# PS_DDR.net
KiCad netlist of a schematic drawn in Altium Designer
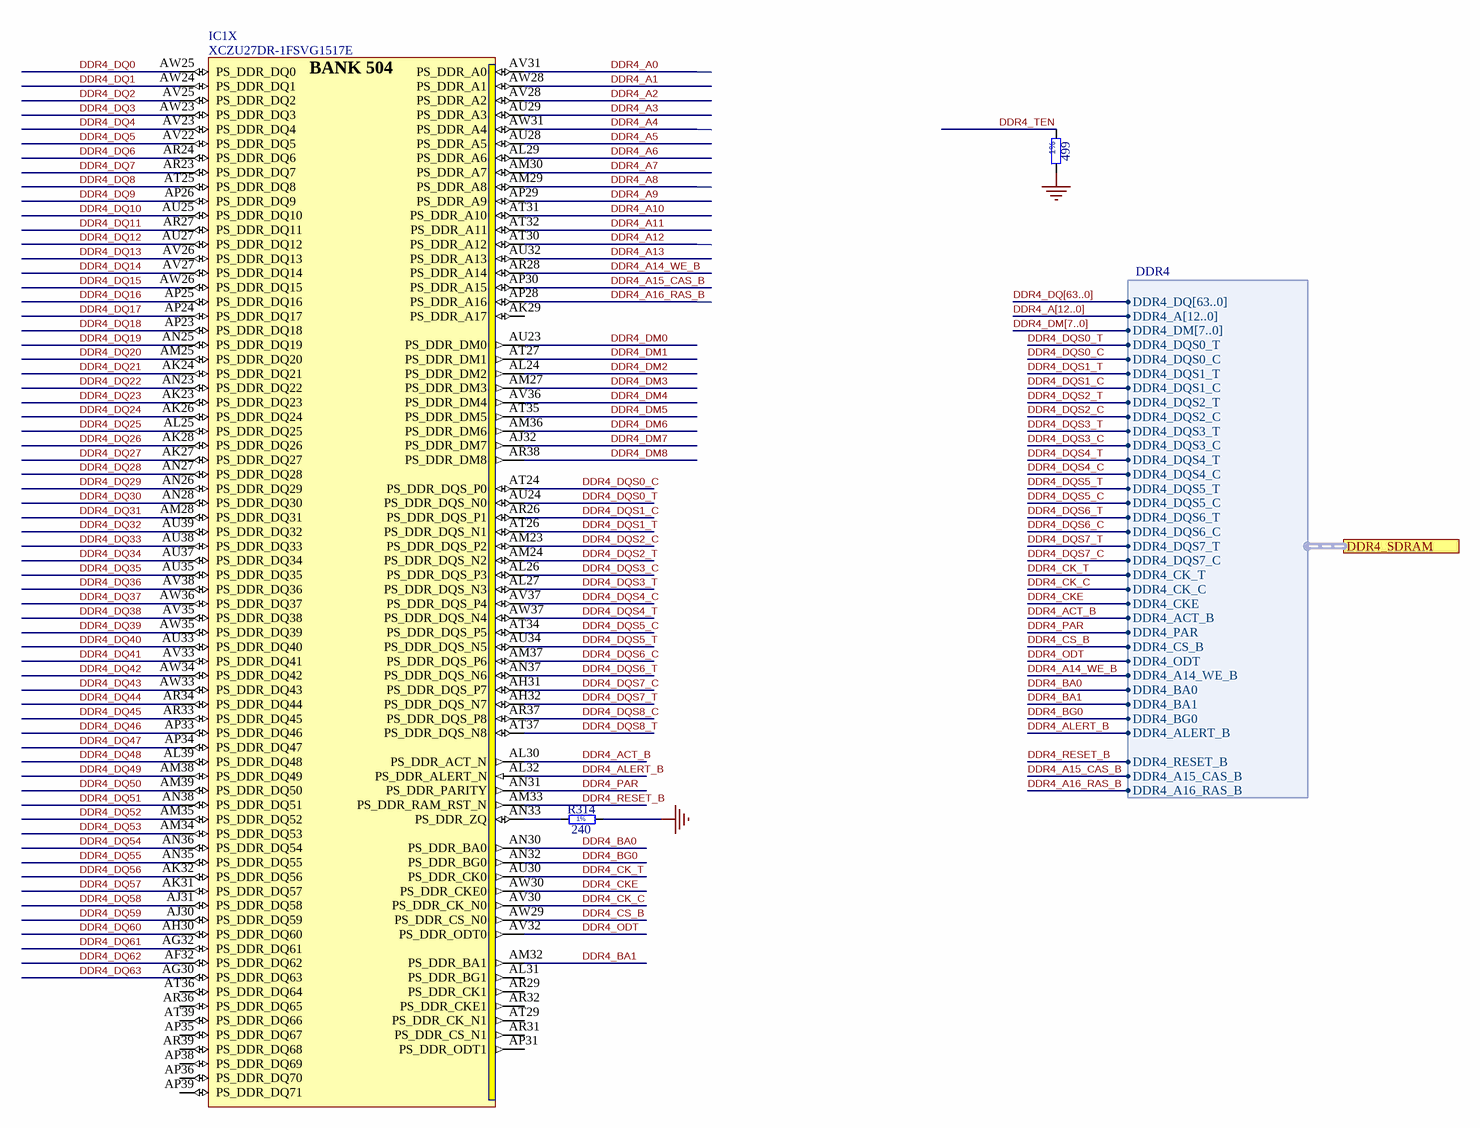
[diagram p0: PS_DDR.SchDoc]

(export (version "E")
  (design (tool "Eeschema 10.0.6"))
  (components
    (comp (ref "IC1")
      (value "XCZU27DR-1FSVG1517E")
      (footprint "XILINX_FSVG1517 (XCZU27DR)")
      (fields (field (name "MANUFACTURER") "XILINX") (field (name "AUTHOR") "CERN DEM MR"))
      (libsource (lib "ICs And Semiconductors") (part "XCZU27DR-1FSVG1517E"))
    )
    (comp (ref "R314")
      (value "240")
      (footprint "RESC1005X40N")
      (description "Resistor - 1%")
      (fields
        (field (name "MANUFACTURER PART NUMBER") "R0402_240R_1%_0.0625W_100PPM")
        (field (name "MANUFACTURER") "GENERIC")
        (field (name "AUTHOR") "CERN DEM JLC")
      )
      (libsource (lib "Resistors") (part "Resistor - 1%"))
    )
    (comp (ref "R629")
      (value "499")
      (fields
        (field (name "$$NOTCOMMONPROPERTY_GENERAL PART NUMBER") "R0402_499R_1%_0.063W_100PPM")
        (field (name "$$NOTCOMMONPROPERTY_MANUFACTURER1 PART NUMBER") "RC0402FR-07499RL")
        (field (name "MANUFACTURER PART NUMBER") "R0402_499R_1%_0.0625W_100PPM")
      )
      (libsource (lib "altium-import") (part "root_1__*"))
    )
  )
  (nets
    (net (code "2") (name "/DDR4_A0") (class "Default")
      (node (ref "IC1") (pin "AV31") (pinfunction "PS_DDR_A0_AV31") (pintype "bidirectional"))
    )
    (net (code "3") (name "/DDR4_A1") (class "Default")
      (node (ref "IC1") (pin "AW28") (pinfunction "PS_DDR_A1_AW28") (pintype "bidirectional"))
    )
    (net (code "4") (name "/DDR4_A2") (class "Default")
      (node (ref "IC1") (pin "AV28") (pinfunction "PS_DDR_A2_AV28") (pintype "bidirectional"))
    )
    (net (code "5") (name "/DDR4_A3") (class "Default")
      (node (ref "IC1") (pin "AU29") (pinfunction "PS_DDR_A3_AU29") (pintype "bidirectional"))
    )
    (net (code "6") (name "/DDR4_A4") (class "Default")
      (node (ref "IC1") (pin "AW31") (pinfunction "PS_DDR_A4_AW31") (pintype "bidirectional"))
    )
    (net (code "7") (name "/DDR4_A5") (class "Default")
      (node (ref "IC1") (pin "AU28") (pinfunction "PS_DDR_A5_AU28") (pintype "bidirectional"))
    )
    (net (code "8") (name "/DDR4_A6") (class "Default")
      (node (ref "IC1") (pin "AL29") (pinfunction "PS_DDR_A6_AL29") (pintype "bidirectional"))
    )
    (net (code "9") (name "/DDR4_A7") (class "Default")
      (node (ref "IC1") (pin "AM30") (pinfunction "PS_DDR_A7_AM30") (pintype "bidirectional"))
    )
    (net (code "10") (name "/DDR4_A8") (class "Default")
      (node (ref "IC1") (pin "AM29") (pinfunction "PS_DDR_A8_AM29") (pintype "bidirectional"))
    )
    (net (code "11") (name "/DDR4_A9") (class "Default")
      (node (ref "IC1") (pin "AP29") (pinfunction "PS_DDR_A9_AP29") (pintype "bidirectional"))
    )
    (net (code "12") (name "/DDR4_A10") (class "Default")
      (node (ref "IC1") (pin "AT31") (pinfunction "PS_DDR_A10_AT31") (pintype "bidirectional"))
    )
    (net (code "13") (name "/DDR4_A11") (class "Default")
      (node (ref "IC1") (pin "AT32") (pinfunction "PS_DDR_A11_AT32") (pintype "bidirectional"))
    )
    (net (code "14") (name "/DDR4_A12") (class "Default")
      (node (ref "IC1") (pin "AT30") (pinfunction "PS_DDR_A12_AT30") (pintype "bidirectional"))
    )
    (net (code "15") (name "/DDR4_A13") (class "Default")
      (node (ref "IC1") (pin "AU32") (pinfunction "PS_DDR_A13_AU32") (pintype "bidirectional"))
    )
    (net (code "16") (name "/DDR4_A14_WE_B") (class "Default")
      (node (ref "IC1") (pin "AR28") (pinfunction "PS_DDR_A14_AR28") (pintype "bidirectional"))
    )
    (net (code "17") (name "/DDR4_A15_CAS_B") (class "Default")
      (node (ref "IC1") (pin "AP30") (pinfunction "PS_DDR_A15_AP30") (pintype "bidirectional"))
    )
    (net (code "18") (name "/DDR4_A16_RAS_B") (class "Default")
      (node (ref "IC1") (pin "AP28") (pinfunction "PS_DDR_A16_AP28") (pintype "bidirectional"))
    )
    (net (code "19") (name "/DDR4_ACT_B") (class "Default")
      (node (ref "IC1") (pin "AL30") (pinfunction "PS_DDR_ACT_N_AL30") (pintype "output"))
    )
    (net (code "20") (name "/DDR4_ALERT_B") (class "Default")
      (node (ref "IC1") (pin "AL32") (pinfunction "PS_DDR_ALERT_N_AL32") (pintype "input"))
    )
    (net (code "22") (name "/DDR4_BA0") (class "Default")
      (node (ref "IC1") (pin "AN30") (pinfunction "PS_DDR_BA0_AN30") (pintype "output"))
    )
    (net (code "23") (name "/DDR4_BA1") (class "Default")
      (node (ref "IC1") (pin "AM32") (pinfunction "PS_DDR_BA1_AM32") (pintype "output"))
    )
    (net (code "24") (name "/DDR4_BG0") (class "Default")
      (node (ref "IC1") (pin "AN32") (pinfunction "PS_DDR_BG0_AN32") (pintype "output"))
    )
    (net (code "25") (name "/DDR4_CKE") (class "Default")
      (node (ref "IC1") (pin "AW30") (pinfunction "PS_DDR_CKE0_AW30") (pintype "output"))
    )
    (net (code "26") (name "/DDR4_CK_C") (class "Default")
      (node (ref "IC1") (pin "AV30") (pinfunction "PS_DDR_CK_N0_AV30") (pintype "output"))
    )
    (net (code "27") (name "/DDR4_CK_T") (class "Default")
      (node (ref "IC1") (pin "AU30") (pinfunction "PS_DDR_CK0_AU30") (pintype "output"))
    )
    (net (code "28") (name "/DDR4_CS_B") (class "Default")
      (node (ref "IC1") (pin "AW29") (pinfunction "PS_DDR_CS_N0_AW29") (pintype "output"))
    )
    (net (code "29") (name "/DDR4_DM0") (class "Default")
      (node (ref "IC1") (pin "AU23") (pinfunction "PS_DDR_DM0_AU23") (pintype "output"))
    )
    (net (code "30") (name "/DDR4_DM1") (class "Default")
      (node (ref "IC1") (pin "AT27") (pinfunction "PS_DDR_DM1_AT27") (pintype "output"))
    )
    (net (code "31") (name "/DDR4_DM2") (class "Default")
      (node (ref "IC1") (pin "AL24") (pinfunction "PS_DDR_DM2_AL24") (pintype "output"))
    )
    (net (code "32") (name "/DDR4_DM3") (class "Default")
      (node (ref "IC1") (pin "AM27") (pinfunction "PS_DDR_DM3_AM27") (pintype "output"))
    )
    (net (code "33") (name "/DDR4_DM4") (class "Default")
      (node (ref "IC1") (pin "AV36") (pinfunction "PS_DDR_DM4_AV36") (pintype "output"))
    )
    (net (code "34") (name "/DDR4_DM5") (class "Default")
      (node (ref "IC1") (pin "AT35") (pinfunction "PS_DDR_DM5_AT35") (pintype "output"))
    )
    (net (code "35") (name "/DDR4_DM6") (class "Default")
      (node (ref "IC1") (pin "AM36") (pinfunction "PS_DDR_DM6_AM36") (pintype "output"))
    )
    (net (code "36") (name "/DDR4_DM7") (class "Default")
      (node (ref "IC1") (pin "AJ32") (pinfunction "PS_DDR_DM7_AJ32") (pintype "output"))
    )
    (net (code "37") (name "/DDR4_DM8") (class "Default")
      (node (ref "IC1") (pin "AR38") (pinfunction "PS_DDR_DM8_AR38") (pintype "output"))
    )
    (net (code "39") (name "/DDR4_DQ0") (class "Default")
      (node (ref "IC1") (pin "AW25") (pinfunction "PS_DDR_DQ0_AW25") (pintype "bidirectional"))
    )
    (net (code "40") (name "/DDR4_DQ1") (class "Default")
      (node (ref "IC1") (pin "AW24") (pinfunction "PS_DDR_DQ1_AW24") (pintype "bidirectional"))
    )
    (net (code "41") (name "/DDR4_DQ2") (class "Default")
      (node (ref "IC1") (pin "AV25") (pinfunction "PS_DDR_DQ2_AV25") (pintype "bidirectional"))
    )
    (net (code "42") (name "/DDR4_DQ3") (class "Default")
      (node (ref "IC1") (pin "AW23") (pinfunction "PS_DDR_DQ3_AW23") (pintype "bidirectional"))
    )
    (net (code "43") (name "/DDR4_DQ4") (class "Default")
      (node (ref "IC1") (pin "AV23") (pinfunction "PS_DDR_DQ4_AV23") (pintype "bidirectional"))
    )
    (net (code "44") (name "/DDR4_DQ5") (class "Default")
      (node (ref "IC1") (pin "AV22") (pinfunction "PS_DDR_DQ5_AV22") (pintype "bidirectional"))
    )
    (net (code "45") (name "/DDR4_DQ6") (class "Default")
      (node (ref "IC1") (pin "AR24") (pinfunction "PS_DDR_DQ6_AR24") (pintype "bidirectional"))
    )
    (net (code "46") (name "/DDR4_DQ7") (class "Default")
      (node (ref "IC1") (pin "AR23") (pinfunction "PS_DDR_DQ7_AR23") (pintype "bidirectional"))
    )
    (net (code "47") (name "/DDR4_DQ8") (class "Default")
      (node (ref "IC1") (pin "AT25") (pinfunction "PS_DDR_DQ8_AT25") (pintype "bidirectional"))
    )
    (net (code "48") (name "/DDR4_DQ9") (class "Default")
      (node (ref "IC1") (pin "AP26") (pinfunction "PS_DDR_DQ9_AP26") (pintype "bidirectional"))
    )
    (net (code "49") (name "/DDR4_DQ10") (class "Default")
      (node (ref "IC1") (pin "AU25") (pinfunction "PS_DDR_DQ10_AU25") (pintype "bidirectional"))
    )
    (net (code "50") (name "/DDR4_DQ11") (class "Default")
      (node (ref "IC1") (pin "AR27") (pinfunction "PS_DDR_DQ11_AR27") (pintype "bidirectional"))
    )
    (net (code "51") (name "/DDR4_DQ12") (class "Default")
      (node (ref "IC1") (pin "AU27") (pinfunction "PS_DDR_DQ12_AU27") (pintype "bidirectional"))
    )
    (net (code "52") (name "/DDR4_DQ13") (class "Default")
      (node (ref "IC1") (pin "AV26") (pinfunction "PS_DDR_DQ13_AV26") (pintype "bidirectional"))
    )
    (net (code "53") (name "/DDR4_DQ14") (class "Default")
      (node (ref "IC1") (pin "AV27") (pinfunction "PS_DDR_DQ14_AV27") (pintype "bidirectional"))
    )
    (net (code "54") (name "/DDR4_DQ15") (class "Default")
      (node (ref "IC1") (pin "AW26") (pinfunction "PS_DDR_DQ15_AW26") (pintype "bidirectional"))
    )
    (net (code "55") (name "/DDR4_DQ16") (class "Default")
      (node (ref "IC1") (pin "AP25") (pinfunction "PS_DDR_DQ16_AP25") (pintype "bidirectional"))
    )
    (net (code "56") (name "/DDR4_DQ17") (class "Default")
      (node (ref "IC1") (pin "AP24") (pinfunction "PS_DDR_DQ17_AP24") (pintype "bidirectional"))
    )
    (net (code "57") (name "/DDR4_DQ18") (class "Default")
      (node (ref "IC1") (pin "AP23") (pinfunction "PS_DDR_DQ18_AP23") (pintype "bidirectional"))
    )
    (net (code "58") (name "/DDR4_DQ19") (class "Default")
      (node (ref "IC1") (pin "AN25") (pinfunction "PS_DDR_DQ19_AN25") (pintype "bidirectional"))
    )
    (net (code "59") (name "/DDR4_DQ20") (class "Default")
      (node (ref "IC1") (pin "AM25") (pinfunction "PS_DDR_DQ20_AM25") (pintype "bidirectional"))
    )
    (net (code "60") (name "/DDR4_DQ21") (class "Default")
      (node (ref "IC1") (pin "AK24") (pinfunction "PS_DDR_DQ21_AK24") (pintype "bidirectional"))
    )
    (net (code "61") (name "/DDR4_DQ22") (class "Default")
      (node (ref "IC1") (pin "AN23") (pinfunction "PS_DDR_DQ22_AN23") (pintype "bidirectional"))
    )
    (net (code "62") (name "/DDR4_DQ23") (class "Default")
      (node (ref "IC1") (pin "AK23") (pinfunction "PS_DDR_DQ23_AK23") (pintype "bidirectional"))
    )
    (net (code "63") (name "/DDR4_DQ24") (class "Default")
      (node (ref "IC1") (pin "AK26") (pinfunction "PS_DDR_DQ24_AK26") (pintype "bidirectional"))
    )
    (net (code "64") (name "/DDR4_DQ25") (class "Default")
      (node (ref "IC1") (pin "AL25") (pinfunction "PS_DDR_DQ25_AL25") (pintype "bidirectional"))
    )
    (net (code "65") (name "/DDR4_DQ26") (class "Default")
      (node (ref "IC1") (pin "AK28") (pinfunction "PS_DDR_DQ26_AK28") (pintype "bidirectional"))
    )
    (net (code "66") (name "/DDR4_DQ27") (class "Default")
      (node (ref "IC1") (pin "AK27") (pinfunction "PS_DDR_DQ27_AK27") (pintype "bidirectional"))
    )
    (net (code "67") (name "/DDR4_DQ28") (class "Default")
      (node (ref "IC1") (pin "AN27") (pinfunction "PS_DDR_DQ28_AN27") (pintype "bidirectional"))
    )
    (net (code "68") (name "/DDR4_DQ29") (class "Default")
      (node (ref "IC1") (pin "AN26") (pinfunction "PS_DDR_DQ29_AN26") (pintype "bidirectional"))
    )
    (net (code "69") (name "/DDR4_DQ30") (class "Default")
      (node (ref "IC1") (pin "AN28") (pinfunction "PS_DDR_DQ30_AN28") (pintype "bidirectional"))
    )
    (net (code "70") (name "/DDR4_DQ31") (class "Default")
      (node (ref "IC1") (pin "AM28") (pinfunction "PS_DDR_DQ31_AM28") (pintype "bidirectional"))
    )
    (net (code "71") (name "/DDR4_DQ32") (class "Default")
      (node (ref "IC1") (pin "AU39") (pinfunction "PS_DDR_DQ32_AU39") (pintype "bidirectional"))
    )
    (net (code "72") (name "/DDR4_DQ33") (class "Default")
      (node (ref "IC1") (pin "AU38") (pinfunction "PS_DDR_DQ33_AU38") (pintype "bidirectional"))
    )
    (net (code "73") (name "/DDR4_DQ34") (class "Default")
      (node (ref "IC1") (pin "AU37") (pinfunction "PS_DDR_DQ34_AU37") (pintype "bidirectional"))
    )
    (net (code "74") (name "/DDR4_DQ35") (class "Default")
      (node (ref "IC1") (pin "AU35") (pinfunction "PS_DDR_DQ35_AU35") (pintype "bidirectional"))
    )
    (net (code "75") (name "/DDR4_DQ36") (class "Default")
      (node (ref "IC1") (pin "AV38") (pinfunction "PS_DDR_DQ36_AV38") (pintype "bidirectional"))
    )
    (net (code "76") (name "/DDR4_DQ37") (class "Default")
      (node (ref "IC1") (pin "AW36") (pinfunction "PS_DDR_DQ37_AW36") (pintype "bidirectional"))
    )
    (net (code "77") (name "/DDR4_DQ38") (class "Default")
      (node (ref "IC1") (pin "AV35") (pinfunction "PS_DDR_DQ38_AV35") (pintype "bidirectional"))
    )
    (net (code "78") (name "/DDR4_DQ39") (class "Default")
      (node (ref "IC1") (pin "AW35") (pinfunction "PS_DDR_DQ39_AW35") (pintype "bidirectional"))
    )
    (net (code "79") (name "/DDR4_DQ40") (class "Default")
      (node (ref "IC1") (pin "AU33") (pinfunction "PS_DDR_DQ40_AU33") (pintype "bidirectional"))
    )
    (net (code "80") (name "/DDR4_DQ41") (class "Default")
      (node (ref "IC1") (pin "AV33") (pinfunction "PS_DDR_DQ41_AV33") (pintype "bidirectional"))
    )
    (net (code "81") (name "/DDR4_DQ42") (class "Default")
      (node (ref "IC1") (pin "AW34") (pinfunction "PS_DDR_DQ42_AW34") (pintype "bidirectional"))
    )
    (net (code "82") (name "/DDR4_DQ43") (class "Default")
      (node (ref "IC1") (pin "AW33") (pinfunction "PS_DDR_DQ43_AW33") (pintype "bidirectional"))
    )
    (net (code "83") (name "/DDR4_DQ44") (class "Default")
      (node (ref "IC1") (pin "AR34") (pinfunction "PS_DDR_DQ44_AR34") (pintype "bidirectional"))
    )
    (net (code "84") (name "/DDR4_DQ45") (class "Default")
      (node (ref "IC1") (pin "AR33") (pinfunction "PS_DDR_DQ45_AR33") (pintype "bidirectional"))
    )
    (net (code "85") (name "/DDR4_DQ46") (class "Default")
      (node (ref "IC1") (pin "AP33") (pinfunction "PS_DDR_DQ46_AP33") (pintype "bidirectional"))
    )
    (net (code "86") (name "/DDR4_DQ47") (class "Default")
      (node (ref "IC1") (pin "AP34") (pinfunction "PS_DDR_DQ47_AP34") (pintype "bidirectional"))
    )
    (net (code "87") (name "/DDR4_DQ48") (class "Default")
      (node (ref "IC1") (pin "AL39") (pinfunction "PS_DDR_DQ48_AL39") (pintype "bidirectional"))
    )
    (net (code "88") (name "/DDR4_DQ49") (class "Default")
      (node (ref "IC1") (pin "AM38") (pinfunction "PS_DDR_DQ49_AM38") (pintype "bidirectional"))
    )
    (net (code "89") (name "/DDR4_DQ50") (class "Default")
      (node (ref "IC1") (pin "AM39") (pinfunction "PS_DDR_DQ50_AM39") (pintype "bidirectional"))
    )
    (net (code "90") (name "/DDR4_DQ51") (class "Default")
      (node (ref "IC1") (pin "AN38") (pinfunction "PS_DDR_DQ51_AN38") (pintype "bidirectional"))
    )
    (net (code "91") (name "/DDR4_DQ52") (class "Default")
      (node (ref "IC1") (pin "AM35") (pinfunction "PS_DDR_DQ52_AM35") (pintype "bidirectional"))
    )
    (net (code "92") (name "/DDR4_DQ53") (class "Default")
      (node (ref "IC1") (pin "AM34") (pinfunction "PS_DDR_DQ53_AM34") (pintype "bidirectional"))
    )
    (net (code "93") (name "/DDR4_DQ54") (class "Default")
      (node (ref "IC1") (pin "AN36") (pinfunction "PS_DDR_DQ54_AN36") (pintype "bidirectional"))
    )
    (net (code "94") (name "/DDR4_DQ55") (class "Default")
      (node (ref "IC1") (pin "AN35") (pinfunction "PS_DDR_DQ55_AN35") (pintype "bidirectional"))
    )
    (net (code "95") (name "/DDR4_DQ56") (class "Default")
      (node (ref "IC1") (pin "AK32") (pinfunction "PS_DDR_DQ56_AK32") (pintype "bidirectional"))
    )
    (net (code "96") (name "/DDR4_DQ57") (class "Default")
      (node (ref "IC1") (pin "AK31") (pinfunction "PS_DDR_DQ57_AK31") (pintype "bidirectional"))
    )
    (net (code "97") (name "/DDR4_DQ58") (class "Default")
      (node (ref "IC1") (pin "AJ31") (pinfunction "PS_DDR_DQ58_AJ31") (pintype "bidirectional"))
    )
    (net (code "98") (name "/DDR4_DQ59") (class "Default")
      (node (ref "IC1") (pin "AJ30") (pinfunction "PS_DDR_DQ59_AJ30") (pintype "bidirectional"))
    )
    (net (code "99") (name "/DDR4_DQ60") (class "Default")
      (node (ref "IC1") (pin "AH30") (pinfunction "PS_DDR_DQ60_AH30") (pintype "bidirectional"))
    )
    (net (code "100") (name "/DDR4_DQ61") (class "Default")
      (node (ref "IC1") (pin "AG32") (pinfunction "PS_DDR_DQ61_AG32") (pintype "bidirectional"))
    )
    (net (code "101") (name "/DDR4_DQ62") (class "Default")
      (node (ref "IC1") (pin "AF32") (pinfunction "PS_DDR_DQ62_AF32") (pintype "bidirectional"))
    )
    (net (code "102") (name "/DDR4_DQ63") (class "Default")
      (node (ref "IC1") (pin "AG30") (pinfunction "PS_DDR_DQ63_AG30") (pintype "bidirectional"))
    )
    (net (code "103") (name "/DDR4_DQS0_C") (class "Default")
      (node (ref "IC1") (pin "AT24") (pinfunction "PS_DDR_DQS_P0_AT24") (pintype "bidirectional"))
    )
    (net (code "104") (name "/DDR4_DQS0_T") (class "Default")
      (node (ref "IC1") (pin "AU24") (pinfunction "PS_DDR_DQS_N0_AU24") (pintype "bidirectional"))
    )
    (net (code "105") (name "/DDR4_DQS1_C") (class "Default")
      (node (ref "IC1") (pin "AR26") (pinfunction "PS_DDR_DQS_P1_AR26") (pintype "bidirectional"))
    )
    (net (code "106") (name "/DDR4_DQS1_T") (class "Default")
      (node (ref "IC1") (pin "AT26") (pinfunction "PS_DDR_DQS_N1_AT26") (pintype "bidirectional"))
    )
    (net (code "107") (name "/DDR4_DQS2_C") (class "Default")
      (node (ref "IC1") (pin "AM23") (pinfunction "PS_DDR_DQS_P2_AM23") (pintype "bidirectional"))
    )
    (net (code "108") (name "/DDR4_DQS2_T") (class "Default")
      (node (ref "IC1") (pin "AM24") (pinfunction "PS_DDR_DQS_N2_AM24") (pintype "bidirectional"))
    )
    (net (code "109") (name "/DDR4_DQS3_C") (class "Default")
      (node (ref "IC1") (pin "AL26") (pinfunction "PS_DDR_DQS_P3_AL26") (pintype "bidirectional"))
    )
    (net (code "110") (name "/DDR4_DQS3_T") (class "Default")
      (node (ref "IC1") (pin "AL27") (pinfunction "PS_DDR_DQS_N3_AL27") (pintype "bidirectional"))
    )
    (net (code "111") (name "/DDR4_DQS4_C") (class "Default")
      (node (ref "IC1") (pin "AV37") (pinfunction "PS_DDR_DQS_P4_AV37") (pintype "bidirectional"))
    )
    (net (code "112") (name "/DDR4_DQS4_T") (class "Default")
      (node (ref "IC1") (pin "AW37") (pinfunction "PS_DDR_DQS_N4_AW37") (pintype "bidirectional"))
    )
    (net (code "113") (name "/DDR4_DQS5_C") (class "Default")
      (node (ref "IC1") (pin "AT34") (pinfunction "PS_DDR_DQS_P5_AT34") (pintype "bidirectional"))
    )
    (net (code "114") (name "/DDR4_DQS5_T") (class "Default")
      (node (ref "IC1") (pin "AU34") (pinfunction "PS_DDR_DQS_N5_AU34") (pintype "bidirectional"))
    )
    (net (code "115") (name "/DDR4_DQS6_C") (class "Default")
      (node (ref "IC1") (pin "AM37") (pinfunction "PS_DDR_DQS_P6_AM37") (pintype "bidirectional"))
    )
    (net (code "116") (name "/DDR4_DQS6_T") (class "Default")
      (node (ref "IC1") (pin "AN37") (pinfunction "PS_DDR_DQS_N6_AN37") (pintype "bidirectional"))
    )
    (net (code "117") (name "/DDR4_DQS7_C") (class "Default")
      (node (ref "IC1") (pin "AH31") (pinfunction "PS_DDR_DQS_P7_AH31") (pintype "bidirectional"))
    )
    (net (code "118") (name "/DDR4_DQS7_T") (class "Default")
      (node (ref "IC1") (pin "AH32") (pinfunction "PS_DDR_DQS_N7_AH32") (pintype "bidirectional"))
    )
    (net (code "119") (name "/DDR4_DQS8_C") (class "Default")
      (node (ref "IC1") (pin "AR37") (pinfunction "PS_DDR_DQS_P8_AR37") (pintype "bidirectional"))
    )
    (net (code "120") (name "/DDR4_DQS8_T") (class "Default")
      (node (ref "IC1") (pin "AT37") (pinfunction "PS_DDR_DQS_N8_AT37") (pintype "bidirectional"))
    )
    (net (code "122") (name "/DDR4_ODT") (class "Default")
      (node (ref "IC1") (pin "AV32") (pinfunction "PS_DDR_ODT0_AV32") (pintype "output"))
    )
    (net (code "123") (name "/DDR4_PAR") (class "Default")
      (node (ref "IC1") (pin "AN31") (pinfunction "PS_DDR_PARITY_AN31") (pintype "output"))
    )
    (net (code "124") (name "/DDR4_RESET_B") (class "Default")
      (node (ref "IC1") (pin "AM33") (pinfunction "PS_DDR_RAM_RST_N_AM33") (pintype "output"))
    )
    (net (code "125") (name "/DDR4_TEN") (class "Default")
      (node (ref "R629") (pin "2") (pinfunction "2_2") (pintype "passive"))
    )
    (net (code "127") (name "GND") (class "Default")
      (node (ref "R314") (pin "2") (pinfunction "2_2") (pintype "passive"))
      (node (ref "R629") (pin "1") (pinfunction "1_1") (pintype "passive"))
    )
    (net (code "128") (name "Net-(IC1X-PS_DDR_ZQ)") (class "Default")
      (node (ref "IC1") (pin "AN33") (pinfunction "PS_DDR_ZQ_AN33") (pintype "bidirectional"))
      (node (ref "R314") (pin "1") (pinfunction "1_1") (pintype "passive"))
    )
    (net (code "129") (name "unconnected-(IC1X-PS_DDR_A17-PadAK29)") (class "Default")
      (node (ref "IC1") (pin "AK29") (pinfunction "PS_DDR_A17_AK29") (pintype "bidirectional"))
    )
    (net (code "130") (name "unconnected-(IC1X-PS_DDR_BG1-PadAL31)") (class "Default")
      (node (ref "IC1") (pin "AL31") (pinfunction "PS_DDR_BG1_AL31") (pintype "output"))
    )
    (net (code "131") (name "unconnected-(IC1X-PS_DDR_CK1-PadAR29)") (class "Default")
      (node (ref "IC1") (pin "AR29") (pinfunction "PS_DDR_CK1_AR29") (pintype "output"))
    )
    (net (code "132") (name "unconnected-(IC1X-PS_DDR_CKE1-PadAR32)") (class "Default")
      (node (ref "IC1") (pin "AR32") (pinfunction "PS_DDR_CKE1_AR32") (pintype "output"))
    )
    (net (code "133") (name "unconnected-(IC1X-PS_DDR_CK_N1-PadAT29)") (class "Default")
      (node (ref "IC1") (pin "AT29") (pinfunction "PS_DDR_CK_N1_AT29") (pintype "output"))
    )
    (net (code "134") (name "unconnected-(IC1X-PS_DDR_CS_N1-PadAR31)") (class "Default")
      (node (ref "IC1") (pin "AR31") (pinfunction "PS_DDR_CS_N1_AR31") (pintype "output"))
    )
    (net (code "135") (name "unconnected-(IC1X-PS_DDR_DQ64-PadAT36)") (class "Default")
      (node (ref "IC1") (pin "AT36") (pinfunction "PS_DDR_DQ64_AT36") (pintype "bidirectional"))
    )
    (net (code "136") (name "unconnected-(IC1X-PS_DDR_DQ65-PadAR36)") (class "Default")
      (node (ref "IC1") (pin "AR36") (pinfunction "PS_DDR_DQ65_AR36") (pintype "bidirectional"))
    )
    (net (code "137") (name "unconnected-(IC1X-PS_DDR_DQ66-PadAT39)") (class "Default")
      (node (ref "IC1") (pin "AT39") (pinfunction "PS_DDR_DQ66_AT39") (pintype "bidirectional"))
    )
    (net (code "138") (name "unconnected-(IC1X-PS_DDR_DQ67-PadAP35)") (class "Default")
      (node (ref "IC1") (pin "AP35") (pinfunction "PS_DDR_DQ67_AP35") (pintype "bidirectional"))
    )
    (net (code "139") (name "unconnected-(IC1X-PS_DDR_DQ68-PadAR39)") (class "Default")
      (node (ref "IC1") (pin "AR39") (pinfunction "PS_DDR_DQ68_AR39") (pintype "bidirectional"))
    )
    (net (code "140") (name "unconnected-(IC1X-PS_DDR_DQ69-PadAP38)") (class "Default")
      (node (ref "IC1") (pin "AP38") (pinfunction "PS_DDR_DQ69_AP38") (pintype "bidirectional"))
    )
    (net (code "141") (name "unconnected-(IC1X-PS_DDR_DQ70-PadAP36)") (class "Default")
      (node (ref "IC1") (pin "AP36") (pinfunction "PS_DDR_DQ70_AP36") (pintype "bidirectional"))
    )
    (net (code "142") (name "unconnected-(IC1X-PS_DDR_DQ71-PadAP39)") (class "Default")
      (node (ref "IC1") (pin "AP39") (pinfunction "PS_DDR_DQ71_AP39") (pintype "bidirectional"))
    )
    (net (code "143") (name "unconnected-(IC1X-PS_DDR_ODT1-PadAP31)") (class "Default")
      (node (ref "IC1") (pin "AP31") (pinfunction "PS_DDR_ODT1_AP31") (pintype "output"))
    )
  )
)
